# 3a_Motor_Interface.net
KiCad netlist of a schematic drawn in Altium Designer
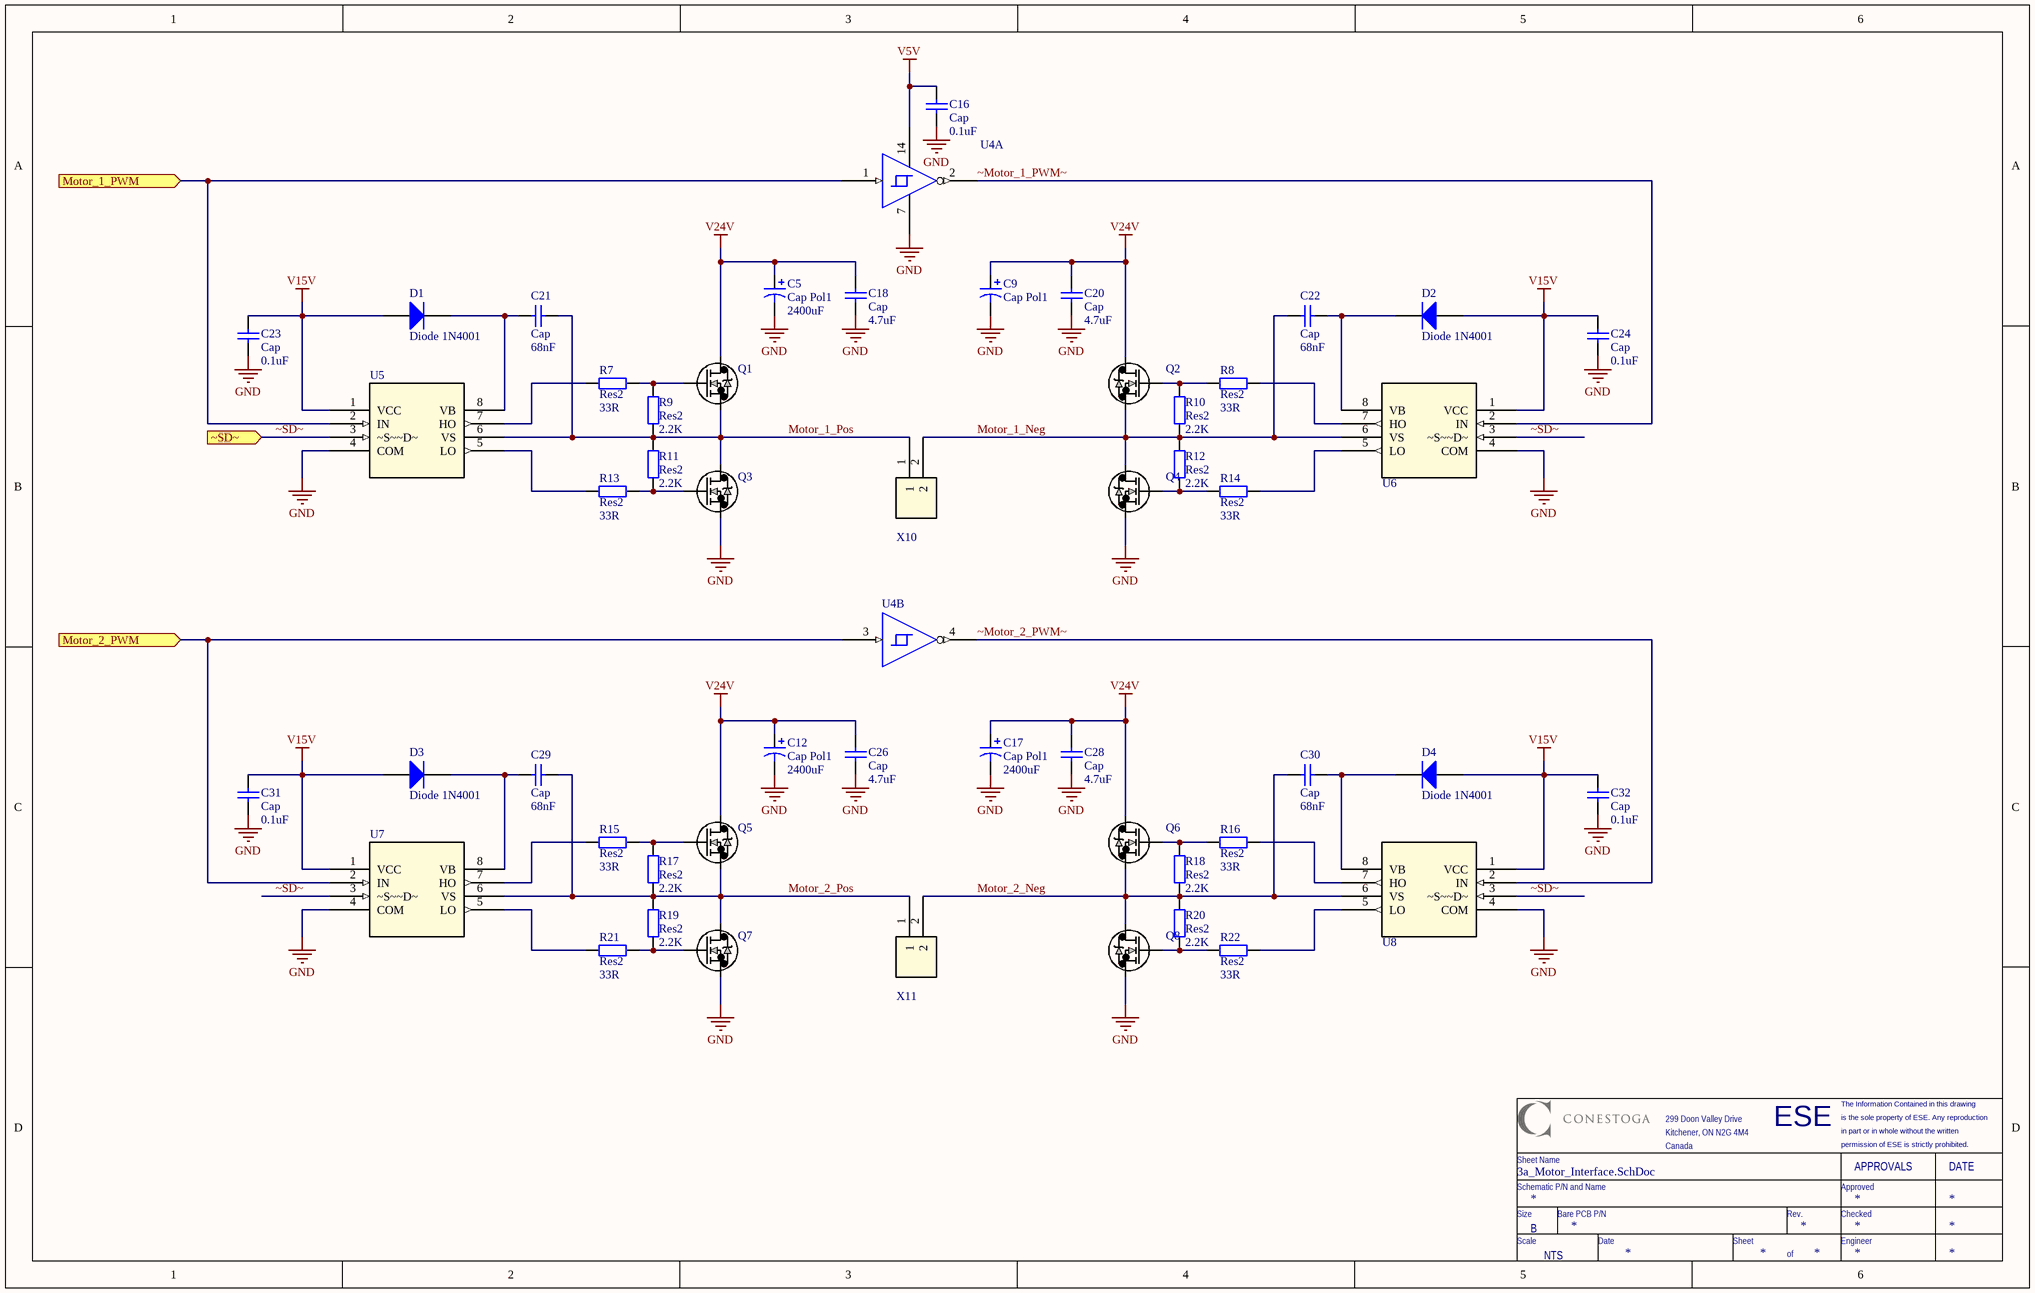
[diagram p0: 3a_Motor_Interface.SchDoc]

(export (version "E")
  (design (tool "Eeschema 10.0.6"))
  (components
    (comp (ref "C5")
      (value "Cap Pol1")
      (footprint "RB7.6-15")
      (description "Polarized Capacitor (Radial)")
      (fields (field (name "ALTIUM_VALUE") "2400uF") (field (name "PUBLISHER") "Altium Limited"))
      (libsource (lib "Miscellaneous Devices") (part "Cap Pol1"))
    )
    (comp (ref "C9")
      (value "Cap Pol1")
      (footprint "RB7.6-15")
      (description "Polarized Capacitor (Radial)")
      (fields (field (name "PUBLISHER") "Altium Limited"))
      (libsource (lib "Miscellaneous Devices") (part "Cap Pol1"))
    )
    (comp (ref "C12")
      (value "Cap Pol1")
      (footprint "RB7.6-15")
      (description "Polarized Capacitor (Radial)")
      (fields (field (name "ALTIUM_VALUE") "2400uF") (field (name "PUBLISHER") "Altium Limited"))
      (libsource (lib "Miscellaneous Devices") (part "Cap Pol1"))
    )
    (comp (ref "C16")
      (value "Cap")
      (footprint "RAD-0.3")
      (description "Capacitor")
      (fields (field (name "ALTIUM_VALUE") "0.1uF") (field (name "PUBLISHER") "Altium Limited"))
      (libsource (lib "Miscellaneous Devices") (part "Cap"))
    )
    (comp (ref "C17")
      (value "Cap Pol1")
      (footprint "RB7.6-15")
      (description "Polarized Capacitor (Radial)")
      (fields (field (name "ALTIUM_VALUE") "2400uF") (field (name "PUBLISHER") "Altium Limited"))
      (libsource (lib "Miscellaneous Devices") (part "Cap Pol1"))
    )
    (comp (ref "C18")
      (value "Cap")
      (footprint "RAD-0.3")
      (description "Capacitor")
      (fields (field (name "ALTIUM_VALUE") "4.7uF") (field (name "PUBLISHER") "Altium Limited"))
      (libsource (lib "Miscellaneous Devices") (part "Cap"))
    )
    (comp (ref "C20")
      (value "Cap")
      (footprint "RAD-0.3")
      (description "Capacitor")
      (fields (field (name "ALTIUM_VALUE") "4.7uF") (field (name "PUBLISHER") "Altium Limited"))
      (libsource (lib "Miscellaneous Devices") (part "Cap"))
    )
    (comp (ref "C21")
      (value "Cap")
      (footprint "RAD-0.3")
      (description "Capacitor")
      (fields (field (name "ALTIUM_VALUE") "68nF") (field (name "PUBLISHER") "Altium Limited"))
      (libsource (lib "Miscellaneous Devices") (part "Cap"))
    )
    (comp (ref "C22")
      (value "Cap")
      (footprint "RAD-0.3")
      (description "Capacitor")
      (fields (field (name "ALTIUM_VALUE") "68nF") (field (name "PUBLISHER") "Altium Limited"))
      (libsource (lib "Miscellaneous Devices") (part "Cap"))
    )
    (comp (ref "C23")
      (value "Cap")
      (footprint "RAD-0.3")
      (description "Capacitor")
      (fields (field (name "ALTIUM_VALUE") "0.1uF") (field (name "PUBLISHER") "Altium Limited"))
      (libsource (lib "Miscellaneous Devices") (part "Cap"))
    )
    (comp (ref "C24")
      (value "Cap")
      (footprint "RAD-0.3")
      (description "Capacitor")
      (fields (field (name "ALTIUM_VALUE") "0.1uF") (field (name "PUBLISHER") "Altium Limited"))
      (libsource (lib "Miscellaneous Devices") (part "Cap"))
    )
    (comp (ref "C26")
      (value "Cap")
      (footprint "RAD-0.3")
      (description "Capacitor")
      (fields (field (name "ALTIUM_VALUE") "4.7uF") (field (name "PUBLISHER") "Altium Limited"))
      (libsource (lib "Miscellaneous Devices") (part "Cap"))
    )
    (comp (ref "C28")
      (value "Cap")
      (footprint "RAD-0.3")
      (description "Capacitor")
      (fields (field (name "ALTIUM_VALUE") "4.7uF") (field (name "PUBLISHER") "Altium Limited"))
      (libsource (lib "Miscellaneous Devices") (part "Cap"))
    )
    (comp (ref "C29")
      (value "Cap")
      (footprint "RAD-0.3")
      (description "Capacitor")
      (fields (field (name "ALTIUM_VALUE") "68nF") (field (name "PUBLISHER") "Altium Limited"))
      (libsource (lib "Miscellaneous Devices") (part "Cap"))
    )
    (comp (ref "C30")
      (value "Cap")
      (footprint "RAD-0.3")
      (description "Capacitor")
      (fields (field (name "ALTIUM_VALUE") "68nF") (field (name "PUBLISHER") "Altium Limited"))
      (libsource (lib "Miscellaneous Devices") (part "Cap"))
    )
    (comp (ref "C31")
      (value "Cap")
      (footprint "RAD-0.3")
      (description "Capacitor")
      (fields (field (name "ALTIUM_VALUE") "0.1uF") (field (name "PUBLISHER") "Altium Limited"))
      (libsource (lib "Miscellaneous Devices") (part "Cap"))
    )
    (comp (ref "C32")
      (value "Cap")
      (footprint "RAD-0.3")
      (description "Capacitor")
      (fields (field (name "ALTIUM_VALUE") "0.1uF") (field (name "PUBLISHER") "Altium Limited"))
      (libsource (lib "Miscellaneous Devices") (part "Cap"))
    )
    (comp (ref "D1")
      (value "Diode 1N4001")
      (footprint "DO-41")
      (description "1 Amp General Purpose Rectifier")
      (fields (field (name "PUBLISHER") "Altium Limited"))
      (libsource (lib "Miscellaneous Devices") (part "Diode 1N4001"))
    )
    (comp (ref "D2")
      (value "Diode 1N4001")
      (footprint "DO-41")
      (description "1 Amp General Purpose Rectifier")
      (fields (field (name "PUBLISHER") "Altium Limited"))
      (libsource (lib "Miscellaneous Devices") (part "Diode 1N4001"))
    )
    (comp (ref "D3")
      (value "Diode 1N4001")
      (footprint "DO-41")
      (description "1 Amp General Purpose Rectifier")
      (fields (field (name "PUBLISHER") "Altium Limited"))
      (libsource (lib "Miscellaneous Devices") (part "Diode 1N4001"))
    )
    (comp (ref "D4")
      (value "Diode 1N4001")
      (footprint "DO-41")
      (description "1 Amp General Purpose Rectifier")
      (fields (field (name "PUBLISHER") "Altium Limited"))
      (libsource (lib "Miscellaneous Devices") (part "Diode 1N4001"))
    )
    (comp (ref "Q1")
      (value "STP100N6F7")
      (footprint "thomas_lib:TO-220")
      (fields (field (name "DIGI-KEY_PART_NUMBER") "497-15888-5-ND"))
      (libsource (lib "thomas_lib") (part "STP100N6F7"))
    )
    (comp (ref "Q2")
      (value "STP100N6F7")
      (footprint "thomas_lib:TO-220")
      (fields (field (name "DIGI-KEY_PART_NUMBER") "497-15888-5-ND"))
      (libsource (lib "thomas_lib") (part "STP100N6F7"))
    )
    (comp (ref "Q3")
      (value "STP100N6F7")
      (footprint "thomas_lib:TO-220")
      (fields (field (name "DIGI-KEY_PART_NUMBER") "497-15888-5-ND"))
      (libsource (lib "thomas_lib") (part "STP100N6F7"))
    )
    (comp (ref "Q4")
      (value "STP100N6F7")
      (footprint "thomas_lib:TO-220")
      (fields (field (name "DIGI-KEY_PART_NUMBER") "497-15888-5-ND"))
      (libsource (lib "thomas_lib") (part "STP100N6F7"))
    )
    (comp (ref "Q5")
      (value "STP100N6F7")
      (footprint "thomas_lib:TO-220")
      (fields (field (name "DIGI-KEY_PART_NUMBER") "497-15888-5-ND"))
      (libsource (lib "thomas_lib") (part "STP100N6F7"))
    )
    (comp (ref "Q6")
      (value "STP100N6F7")
      (footprint "thomas_lib:TO-220")
      (fields (field (name "DIGI-KEY_PART_NUMBER") "497-15888-5-ND"))
      (libsource (lib "thomas_lib") (part "STP100N6F7"))
    )
    (comp (ref "Q7")
      (value "STP100N6F7")
      (footprint "thomas_lib:TO-220")
      (fields (field (name "DIGI-KEY_PART_NUMBER") "497-15888-5-ND"))
      (libsource (lib "thomas_lib") (part "STP100N6F7"))
    )
    (comp (ref "Q8")
      (value "STP100N6F7")
      (footprint "thomas_lib:TO-220")
      (fields (field (name "DIGI-KEY_PART_NUMBER") "497-15888-5-ND"))
      (libsource (lib "thomas_lib") (part "STP100N6F7"))
    )
    (comp (ref "R7")
      (value "Res2")
      (footprint "AXIAL-0.4")
      (description "Resistor")
      (fields (field (name "ALTIUM_VALUE") "33R") (field (name "PUBLISHER") "Altium Limited"))
      (libsource (lib "") (part "Res2_1"))
    )
    (comp (ref "R8")
      (value "Res2")
      (footprint "AXIAL-0.4")
      (description "Resistor")
      (fields (field (name "ALTIUM_VALUE") "33R") (field (name "PUBLISHER") "Altium Limited"))
      (libsource (lib "") (part "Res2_2"))
    )
    (comp (ref "R9")
      (value "Res2")
      (footprint "AXIAL-0.4")
      (description "Resistor")
      (fields (field (name "ALTIUM_VALUE") "2.2K") (field (name "PUBLISHER") "Altium Limited"))
      (libsource (lib "Miscellaneous Devices") (part "Res2"))
    )
    (comp (ref "R10")
      (value "Res2")
      (footprint "AXIAL-0.4")
      (description "Resistor")
      (fields (field (name "ALTIUM_VALUE") "2.2K") (field (name "PUBLISHER") "Altium Limited"))
      (libsource (lib "") (part "Res2_1"))
    )
    (comp (ref "R11")
      (value "Res2")
      (footprint "AXIAL-0.4")
      (description "Resistor")
      (fields (field (name "ALTIUM_VALUE") "2.2K") (field (name "PUBLISHER") "Altium Limited"))
      (libsource (lib "Miscellaneous Devices") (part "Res2"))
    )
    (comp (ref "R12")
      (value "Res2")
      (footprint "AXIAL-0.4")
      (description "Resistor")
      (fields (field (name "ALTIUM_VALUE") "2.2K") (field (name "PUBLISHER") "Altium Limited"))
      (libsource (lib "") (part "Res2_1"))
    )
    (comp (ref "R13")
      (value "Res2")
      (footprint "AXIAL-0.4")
      (description "Resistor")
      (fields (field (name "ALTIUM_VALUE") "33R") (field (name "PUBLISHER") "Altium Limited"))
      (libsource (lib "") (part "Res2_1"))
    )
    (comp (ref "R14")
      (value "Res2")
      (footprint "AXIAL-0.4")
      (description "Resistor")
      (fields (field (name "ALTIUM_VALUE") "33R") (field (name "PUBLISHER") "Altium Limited"))
      (libsource (lib "") (part "Res2_2"))
    )
    (comp (ref "R15")
      (value "Res2")
      (footprint "AXIAL-0.4")
      (description "Resistor")
      (fields (field (name "ALTIUM_VALUE") "33R") (field (name "PUBLISHER") "Altium Limited"))
      (libsource (lib "") (part "Res2_1"))
    )
    (comp (ref "R16")
      (value "Res2")
      (footprint "AXIAL-0.4")
      (description "Resistor")
      (fields (field (name "ALTIUM_VALUE") "33R") (field (name "PUBLISHER") "Altium Limited"))
      (libsource (lib "") (part "Res2_2"))
    )
    (comp (ref "R17")
      (value "Res2")
      (footprint "AXIAL-0.4")
      (description "Resistor")
      (fields (field (name "ALTIUM_VALUE") "2.2K") (field (name "PUBLISHER") "Altium Limited"))
      (libsource (lib "Miscellaneous Devices") (part "Res2"))
    )
    (comp (ref "R18")
      (value "Res2")
      (footprint "AXIAL-0.4")
      (description "Resistor")
      (fields (field (name "ALTIUM_VALUE") "2.2K") (field (name "PUBLISHER") "Altium Limited"))
      (libsource (lib "") (part "Res2_1"))
    )
    (comp (ref "R19")
      (value "Res2")
      (footprint "AXIAL-0.4")
      (description "Resistor")
      (fields (field (name "ALTIUM_VALUE") "2.2K") (field (name "PUBLISHER") "Altium Limited"))
      (libsource (lib "Miscellaneous Devices") (part "Res2"))
    )
    (comp (ref "R20")
      (value "Res2")
      (footprint "AXIAL-0.4")
      (description "Resistor")
      (fields (field (name "ALTIUM_VALUE") "2.2K") (field (name "PUBLISHER") "Altium Limited"))
      (libsource (lib "") (part "Res2_1"))
    )
    (comp (ref "R21")
      (value "Res2")
      (footprint "AXIAL-0.4")
      (description "Resistor")
      (fields (field (name "ALTIUM_VALUE") "33R") (field (name "PUBLISHER") "Altium Limited"))
      (libsource (lib "") (part "Res2_1"))
    )
    (comp (ref "R22")
      (value "Res2")
      (footprint "AXIAL-0.4")
      (description "Resistor")
      (fields (field (name "ALTIUM_VALUE") "33R") (field (name "PUBLISHER") "Altium Limited"))
      (libsource (lib "") (part "Res2_2"))
    )
    (comp (ref "U4")
      (value "IC HEX SCHMITT-TRIG INV 14-DIP")
      (footprint "14-DIP")
      (fields
        (field (name "DIGI-KEY_PART_NUMBER") "296-4368-5-ND")
        (field (name "MANUFACTUER_PART_NUMBER") "SN74ACT14N")
        (field (name "MANUFACTURER") "Texas Instruments")
      )
      (libsource (lib "thomas_lib") (part "IC HEX SCHMITT-TRIG INV 14-DIP"))
    )
    (comp (ref "U5")
      (value "IC DRIVER HALF BRIDGE 8DIP")
      (footprint "thomas_lib:8-DIP")
      (fields
        (field (name "MANUFACTURER_PART_NUMBER") "IR2109PBF")
        (field (name "DIGI-KEY_PART_NUMBER") "IR2109PBF-ND")
        (field (name "MANUFACTURER") "Infineon Technologies")
      )
      (libsource (lib "") (part "IC DRIVER HALF BRIDGE 8DIP_1"))
    )
    (comp (ref "U6")
      (value "IC DRIVER HALF BRIDGE 8DIP")
      (footprint "thomas_lib:8-DIP")
      (fields
        (field (name "MANUFACTURER_PART_NUMBER") "IR2109PBF")
        (field (name "DIGI-KEY_PART_NUMBER") "IR2109PBF-ND")
        (field (name "MANUFACTURER") "Infineon Technologies")
      )
      (libsource (lib "thomas_lib") (part "IC DRIVER HALF BRIDGE 8DIP"))
    )
    (comp (ref "U7")
      (value "IC DRIVER HALF BRIDGE 8DIP")
      (footprint "thomas_lib:8-DIP")
      (fields
        (field (name "MANUFACTURER_PART_NUMBER") "IR2109PBF")
        (field (name "DIGI-KEY_PART_NUMBER") "IR2109PBF-ND")
        (field (name "MANUFACTURER") "Infineon Technologies")
      )
      (libsource (lib "") (part "IC DRIVER HALF BRIDGE 8DIP_1"))
    )
    (comp (ref "U8")
      (value "IC DRIVER HALF BRIDGE 8DIP")
      (footprint "thomas_lib:8-DIP")
      (fields
        (field (name "MANUFACTURER_PART_NUMBER") "IR2109PBF")
        (field (name "DIGI-KEY_PART_NUMBER") "IR2109PBF-ND")
        (field (name "MANUFACTURER") "Infineon Technologies")
      )
      (libsource (lib "thomas_lib") (part "IC DRIVER HALF BRIDGE 8DIP"))
    )
    (comp (ref "X10")
      (value "TERM BLOCK HDR 2POS VERT 3.5MM")
      (footprint "WR-TBL-3211 2")
      (fields
        (field (name "DIGIKEY_PART_NUMBER") "732-2763-ND")
        (field (name "MANUFACTURER_PART_NUMBER") "691321100002")
        (field (name "MANUFACTURER") "Wurth Electronics Inc")
      )
      (libsource (lib "thomas_lib") (part "TERM BLOCK HDR 2POS VERT 3.5MM"))
    )
    (comp (ref "X11")
      (value "TERM BLOCK HDR 2POS VERT 3.5MM")
      (footprint "WR-TBL-3211 2")
      (fields
        (field (name "DIGIKEY_PART_NUMBER") "732-2763-ND")
        (field (name "MANUFACTURER_PART_NUMBER") "691321100002")
        (field (name "MANUFACTURER") "Wurth Electronics Inc")
      )
      (libsource (lib "thomas_lib") (part "TERM BLOCK HDR 2POS VERT 3.5MM"))
    )
  )
  (nets
    (net (code "1") (name "/Motor_1_Neg") (class "Default")
      (node (ref "C22") (pin "1") (pinfunction "1_1") (pintype "passive"))
      (node (ref "Q2") (pin "3") (pinfunction "3_3") (pintype "passive"))
      (node (ref "Q4") (pin "2") (pinfunction "2_2") (pintype "passive"))
      (node (ref "R10") (pin "2") (pinfunction "2_2") (pintype "passive"))
      (node (ref "R12") (pin "1") (pinfunction "1_1") (pintype "passive"))
      (node (ref "U6") (pin "6") (pinfunction "VS_6") (pintype "power_in"))
      (node (ref "X10") (pin "2") (pinfunction "2_2") (pintype "passive"))
    )
    (net (code "2") (name "/Motor_1_PWM") (class "Default")
      (node (ref "U4") (pin "1") (pinfunction "A_1") (pintype "input"))
      (node (ref "U5") (pin "2") (pinfunction "IN_2") (pintype "input"))
    )
    (net (code "3") (name "/Motor_1_Pos") (class "Default")
      (node (ref "C21") (pin "1") (pinfunction "1_1") (pintype "passive"))
      (node (ref "Q1") (pin "3") (pinfunction "3_3") (pintype "passive"))
      (node (ref "Q3") (pin "2") (pinfunction "2_2") (pintype "passive"))
      (node (ref "R11") (pin "1") (pinfunction "1_1") (pintype "passive"))
      (node (ref "R9") (pin "2") (pinfunction "2_2") (pintype "passive"))
      (node (ref "U5") (pin "6") (pinfunction "VS_6") (pintype "power_in"))
      (node (ref "X10") (pin "1") (pinfunction "1_1") (pintype "passive"))
    )
    (net (code "4") (name "/Motor_2_Neg") (class "Default")
      (node (ref "C30") (pin "1") (pinfunction "1_1") (pintype "passive"))
      (node (ref "Q6") (pin "3") (pinfunction "3_3") (pintype "passive"))
      (node (ref "Q8") (pin "2") (pinfunction "2_2") (pintype "passive"))
      (node (ref "R18") (pin "2") (pinfunction "2_2") (pintype "passive"))
      (node (ref "R20") (pin "1") (pinfunction "1_1") (pintype "passive"))
      (node (ref "U8") (pin "6") (pinfunction "VS_6") (pintype "power_in"))
      (node (ref "X11") (pin "2") (pinfunction "2_2") (pintype "passive"))
    )
    (net (code "5") (name "/Motor_2_PWM") (class "Default")
      (node (ref "U4") (pin "3") (pinfunction "A_3") (pintype "input"))
      (node (ref "U7") (pin "2") (pinfunction "IN_2") (pintype "input"))
    )
    (net (code "6") (name "/Motor_2_Pos") (class "Default")
      (node (ref "C29") (pin "1") (pinfunction "1_1") (pintype "passive"))
      (node (ref "Q5") (pin "3") (pinfunction "3_3") (pintype "passive"))
      (node (ref "Q7") (pin "2") (pinfunction "2_2") (pintype "passive"))
      (node (ref "R17") (pin "2") (pinfunction "2_2") (pintype "passive"))
      (node (ref "R19") (pin "1") (pinfunction "1_1") (pintype "passive"))
      (node (ref "U7") (pin "6") (pinfunction "VS_6") (pintype "power_in"))
      (node (ref "X11") (pin "1") (pinfunction "1_1") (pintype "passive"))
    )
    (net (code "7") (name "/~Motor_1_PWM~") (class "Default")
      (node (ref "U4") (pin "2") (pinfunction "Y_2") (pintype "output"))
      (node (ref "U6") (pin "2") (pinfunction "IN_2") (pintype "input"))
    )
    (net (code "8") (name "/~Motor_2_PWM~") (class "Default")
      (node (ref "U4") (pin "4") (pinfunction "Y_4") (pintype "output"))
      (node (ref "U8") (pin "2") (pinfunction "IN_2") (pintype "input"))
    )
    (net (code "9") (name "/~SD~") (class "Default")
      (node (ref "U5") (pin "3") (pinfunction "~S~~D~_3") (pintype "input"))
      (node (ref "U6") (pin "3") (pinfunction "~S~~D~_3") (pintype "input"))
      (node (ref "U7") (pin "3") (pinfunction "~S~~D~_3") (pintype "input"))
      (node (ref "U8") (pin "3") (pinfunction "~S~~D~_3") (pintype "input"))
    )
    (net (code "10") (name "GND") (class "Default")
      (node (ref "C12") (pin "2") (pinfunction "2_2") (pintype "passive"))
      (node (ref "C16") (pin "1") (pinfunction "1_1") (pintype "passive"))
      (node (ref "C17") (pin "2") (pinfunction "2_2") (pintype "passive"))
      (node (ref "C18") (pin "1") (pinfunction "1_1") (pintype "passive"))
      (node (ref "C20") (pin "1") (pinfunction "1_1") (pintype "passive"))
      (node (ref "C23") (pin "1") (pinfunction "1_1") (pintype "passive"))
      (node (ref "C24") (pin "1") (pinfunction "1_1") (pintype "passive"))
      (node (ref "C26") (pin "1") (pinfunction "1_1") (pintype "passive"))
      (node (ref "C28") (pin "1") (pinfunction "1_1") (pintype "passive"))
      (node (ref "C31") (pin "1") (pinfunction "1_1") (pintype "passive"))
      (node (ref "C32") (pin "1") (pinfunction "1_1") (pintype "passive"))
      (node (ref "C5") (pin "2") (pinfunction "2_2") (pintype "passive"))
      (node (ref "C9") (pin "2") (pinfunction "2_2") (pintype "passive"))
      (node (ref "Q3") (pin "3") (pinfunction "3_3") (pintype "passive"))
      (node (ref "Q4") (pin "3") (pinfunction "3_3") (pintype "passive"))
      (node (ref "Q7") (pin "3") (pinfunction "3_3") (pintype "passive"))
      (node (ref "Q8") (pin "3") (pinfunction "3_3") (pintype "passive"))
      (node (ref "U4") (pin "7") (pinfunction "GND_POWER_7") (pintype "power_in"))
      (node (ref "U5") (pin "4") (pinfunction "COM_4") (pintype "power_in"))
      (node (ref "U6") (pin "4") (pinfunction "COM_4") (pintype "power_in"))
      (node (ref "U7") (pin "4") (pinfunction "COM_4") (pintype "power_in"))
      (node (ref "U8") (pin "4") (pinfunction "COM_4") (pintype "power_in"))
    )
    (net (code "11") (name "Net-(D1-K)") (class "Default")
      (node (ref "C21") (pin "2") (pinfunction "2_2") (pintype "passive"))
      (node (ref "D1") (pin "2") (pinfunction "K_2") (pintype "passive"))
      (node (ref "U5") (pin "8") (pinfunction "VB_8") (pintype "power_in"))
    )
    (net (code "12") (name "Net-(D2-K)") (class "Default")
      (node (ref "C22") (pin "2") (pinfunction "2_2") (pintype "passive"))
      (node (ref "D2") (pin "2") (pinfunction "K_2") (pintype "passive"))
      (node (ref "U6") (pin "8") (pinfunction "VB_8") (pintype "power_in"))
    )
    (net (code "13") (name "Net-(D3-K)") (class "Default")
      (node (ref "C29") (pin "2") (pinfunction "2_2") (pintype "passive"))
      (node (ref "D3") (pin "2") (pinfunction "K_2") (pintype "passive"))
      (node (ref "U7") (pin "8") (pinfunction "VB_8") (pintype "power_in"))
    )
    (net (code "14") (name "Net-(D4-K)") (class "Default")
      (node (ref "C30") (pin "2") (pinfunction "2_2") (pintype "passive"))
      (node (ref "D4") (pin "2") (pinfunction "K_2") (pintype "passive"))
      (node (ref "U8") (pin "8") (pinfunction "VB_8") (pintype "power_in"))
    )
    (net (code "15") (name "Net-(Q1-Pad1)") (class "Default")
      (node (ref "Q1") (pin "1") (pinfunction "1_1") (pintype "passive"))
      (node (ref "R7") (pin "1") (pinfunction "1_1") (pintype "passive"))
      (node (ref "R9") (pin "1") (pinfunction "1_1") (pintype "passive"))
    )
    (net (code "16") (name "Net-(Q2-Pad1)") (class "Default")
      (node (ref "Q2") (pin "1") (pinfunction "1_1") (pintype "passive"))
      (node (ref "R10") (pin "1") (pinfunction "1_1") (pintype "passive"))
      (node (ref "R8") (pin "1") (pinfunction "1_1") (pintype "passive"))
    )
    (net (code "17") (name "Net-(Q3-Pad1)") (class "Default")
      (node (ref "Q3") (pin "1") (pinfunction "1_1") (pintype "passive"))
      (node (ref "R11") (pin "2") (pinfunction "2_2") (pintype "passive"))
      (node (ref "R13") (pin "1") (pinfunction "1_1") (pintype "passive"))
    )
    (net (code "18") (name "Net-(Q4-Pad1)") (class "Default")
      (node (ref "Q4") (pin "1") (pinfunction "1_1") (pintype "passive"))
      (node (ref "R12") (pin "2") (pinfunction "2_2") (pintype "passive"))
      (node (ref "R14") (pin "1") (pinfunction "1_1") (pintype "passive"))
    )
    (net (code "19") (name "Net-(Q5-Pad1)") (class "Default")
      (node (ref "Q5") (pin "1") (pinfunction "1_1") (pintype "passive"))
      (node (ref "R15") (pin "1") (pinfunction "1_1") (pintype "passive"))
      (node (ref "R17") (pin "1") (pinfunction "1_1") (pintype "passive"))
    )
    (net (code "20") (name "Net-(Q6-Pad1)") (class "Default")
      (node (ref "Q6") (pin "1") (pinfunction "1_1") (pintype "passive"))
      (node (ref "R16") (pin "1") (pinfunction "1_1") (pintype "passive"))
      (node (ref "R18") (pin "1") (pinfunction "1_1") (pintype "passive"))
    )
    (net (code "21") (name "Net-(Q7-Pad1)") (class "Default")
      (node (ref "Q7") (pin "1") (pinfunction "1_1") (pintype "passive"))
      (node (ref "R19") (pin "2") (pinfunction "2_2") (pintype "passive"))
      (node (ref "R21") (pin "1") (pinfunction "1_1") (pintype "passive"))
    )
    (net (code "22") (name "Net-(Q8-Pad1)") (class "Default")
      (node (ref "Q8") (pin "1") (pinfunction "1_1") (pintype "passive"))
      (node (ref "R20") (pin "2") (pinfunction "2_2") (pintype "passive"))
      (node (ref "R22") (pin "1") (pinfunction "1_1") (pintype "passive"))
    )
    (net (code "23") (name "Net-(U5-HO)") (class "Default")
      (node (ref "R7") (pin "2") (pinfunction "2_2") (pintype "passive"))
      (node (ref "U5") (pin "7") (pinfunction "HO_7") (pintype "output"))
    )
    (net (code "24") (name "Net-(U5-LO)") (class "Default")
      (node (ref "R13") (pin "2") (pinfunction "2_2") (pintype "passive"))
      (node (ref "U5") (pin "5") (pinfunction "LO_5") (pintype "output"))
    )
    (net (code "25") (name "Net-(U6-HO)") (class "Default")
      (node (ref "R8") (pin "2") (pinfunction "2_2") (pintype "passive"))
      (node (ref "U6") (pin "7") (pinfunction "HO_7") (pintype "output"))
    )
    (net (code "26") (name "Net-(U6-LO)") (class "Default")
      (node (ref "R14") (pin "2") (pinfunction "2_2") (pintype "passive"))
      (node (ref "U6") (pin "5") (pinfunction "LO_5") (pintype "output"))
    )
    (net (code "27") (name "Net-(U7-HO)") (class "Default")
      (node (ref "R15") (pin "2") (pinfunction "2_2") (pintype "passive"))
      (node (ref "U7") (pin "7") (pinfunction "HO_7") (pintype "output"))
    )
    (net (code "28") (name "Net-(U7-LO)") (class "Default")
      (node (ref "R21") (pin "2") (pinfunction "2_2") (pintype "passive"))
      (node (ref "U7") (pin "5") (pinfunction "LO_5") (pintype "output"))
    )
    (net (code "29") (name "Net-(U8-HO)") (class "Default")
      (node (ref "R16") (pin "2") (pinfunction "2_2") (pintype "passive"))
      (node (ref "U8") (pin "7") (pinfunction "HO_7") (pintype "output"))
    )
    (net (code "30") (name "Net-(U8-LO)") (class "Default")
      (node (ref "R22") (pin "2") (pinfunction "2_2") (pintype "passive"))
      (node (ref "U8") (pin "5") (pinfunction "LO_5") (pintype "output"))
    )
    (net (code "31") (name "V5V") (class "Default")
      (node (ref "C16") (pin "2") (pinfunction "2_2") (pintype "passive"))
      (node (ref "U4") (pin "14") (pinfunction "VCC_14") (pintype "power_in"))
    )
    (net (code "32") (name "V15V") (class "Default")
      (node (ref "C23") (pin "2") (pinfunction "2_2") (pintype "passive"))
      (node (ref "C24") (pin "2") (pinfunction "2_2") (pintype "passive"))
      (node (ref "C31") (pin "2") (pinfunction "2_2") (pintype "passive"))
      (node (ref "C32") (pin "2") (pinfunction "2_2") (pintype "passive"))
      (node (ref "D1") (pin "1") (pinfunction "A_1") (pintype "passive"))
      (node (ref "D2") (pin "1") (pinfunction "A_1") (pintype "passive"))
      (node (ref "D3") (pin "1") (pinfunction "A_1") (pintype "passive"))
      (node (ref "D4") (pin "1") (pinfunction "A_1") (pintype "passive"))
      (node (ref "U5") (pin "1") (pinfunction "VCC_1") (pintype "power_in"))
      (node (ref "U6") (pin "1") (pinfunction "VCC_1") (pintype "power_in"))
      (node (ref "U7") (pin "1") (pinfunction "VCC_1") (pintype "power_in"))
      (node (ref "U8") (pin "1") (pinfunction "VCC_1") (pintype "power_in"))
    )
    (net (code "33") (name "V24V") (class "Default")
      (node (ref "C12") (pin "1") (pinfunction "1_1") (pintype "passive"))
      (node (ref "C17") (pin "1") (pinfunction "1_1") (pintype "passive"))
      (node (ref "C18") (pin "2") (pinfunction "2_2") (pintype "passive"))
      (node (ref "C20") (pin "2") (pinfunction "2_2") (pintype "passive"))
      (node (ref "C26") (pin "2") (pinfunction "2_2") (pintype "passive"))
      (node (ref "C28") (pin "2") (pinfunction "2_2") (pintype "passive"))
      (node (ref "C5") (pin "1") (pinfunction "1_1") (pintype "passive"))
      (node (ref "C9") (pin "1") (pinfunction "1_1") (pintype "passive"))
      (node (ref "Q1") (pin "2") (pinfunction "2_2") (pintype "passive"))
      (node (ref "Q2") (pin "2") (pinfunction "2_2") (pintype "passive"))
      (node (ref "Q5") (pin "2") (pinfunction "2_2") (pintype "passive"))
      (node (ref "Q6") (pin "2") (pinfunction "2_2") (pintype "passive"))
    )
  )
)
